# PowerResetBrd.net
KiCad netlist of a schematic drawn in EAGLE
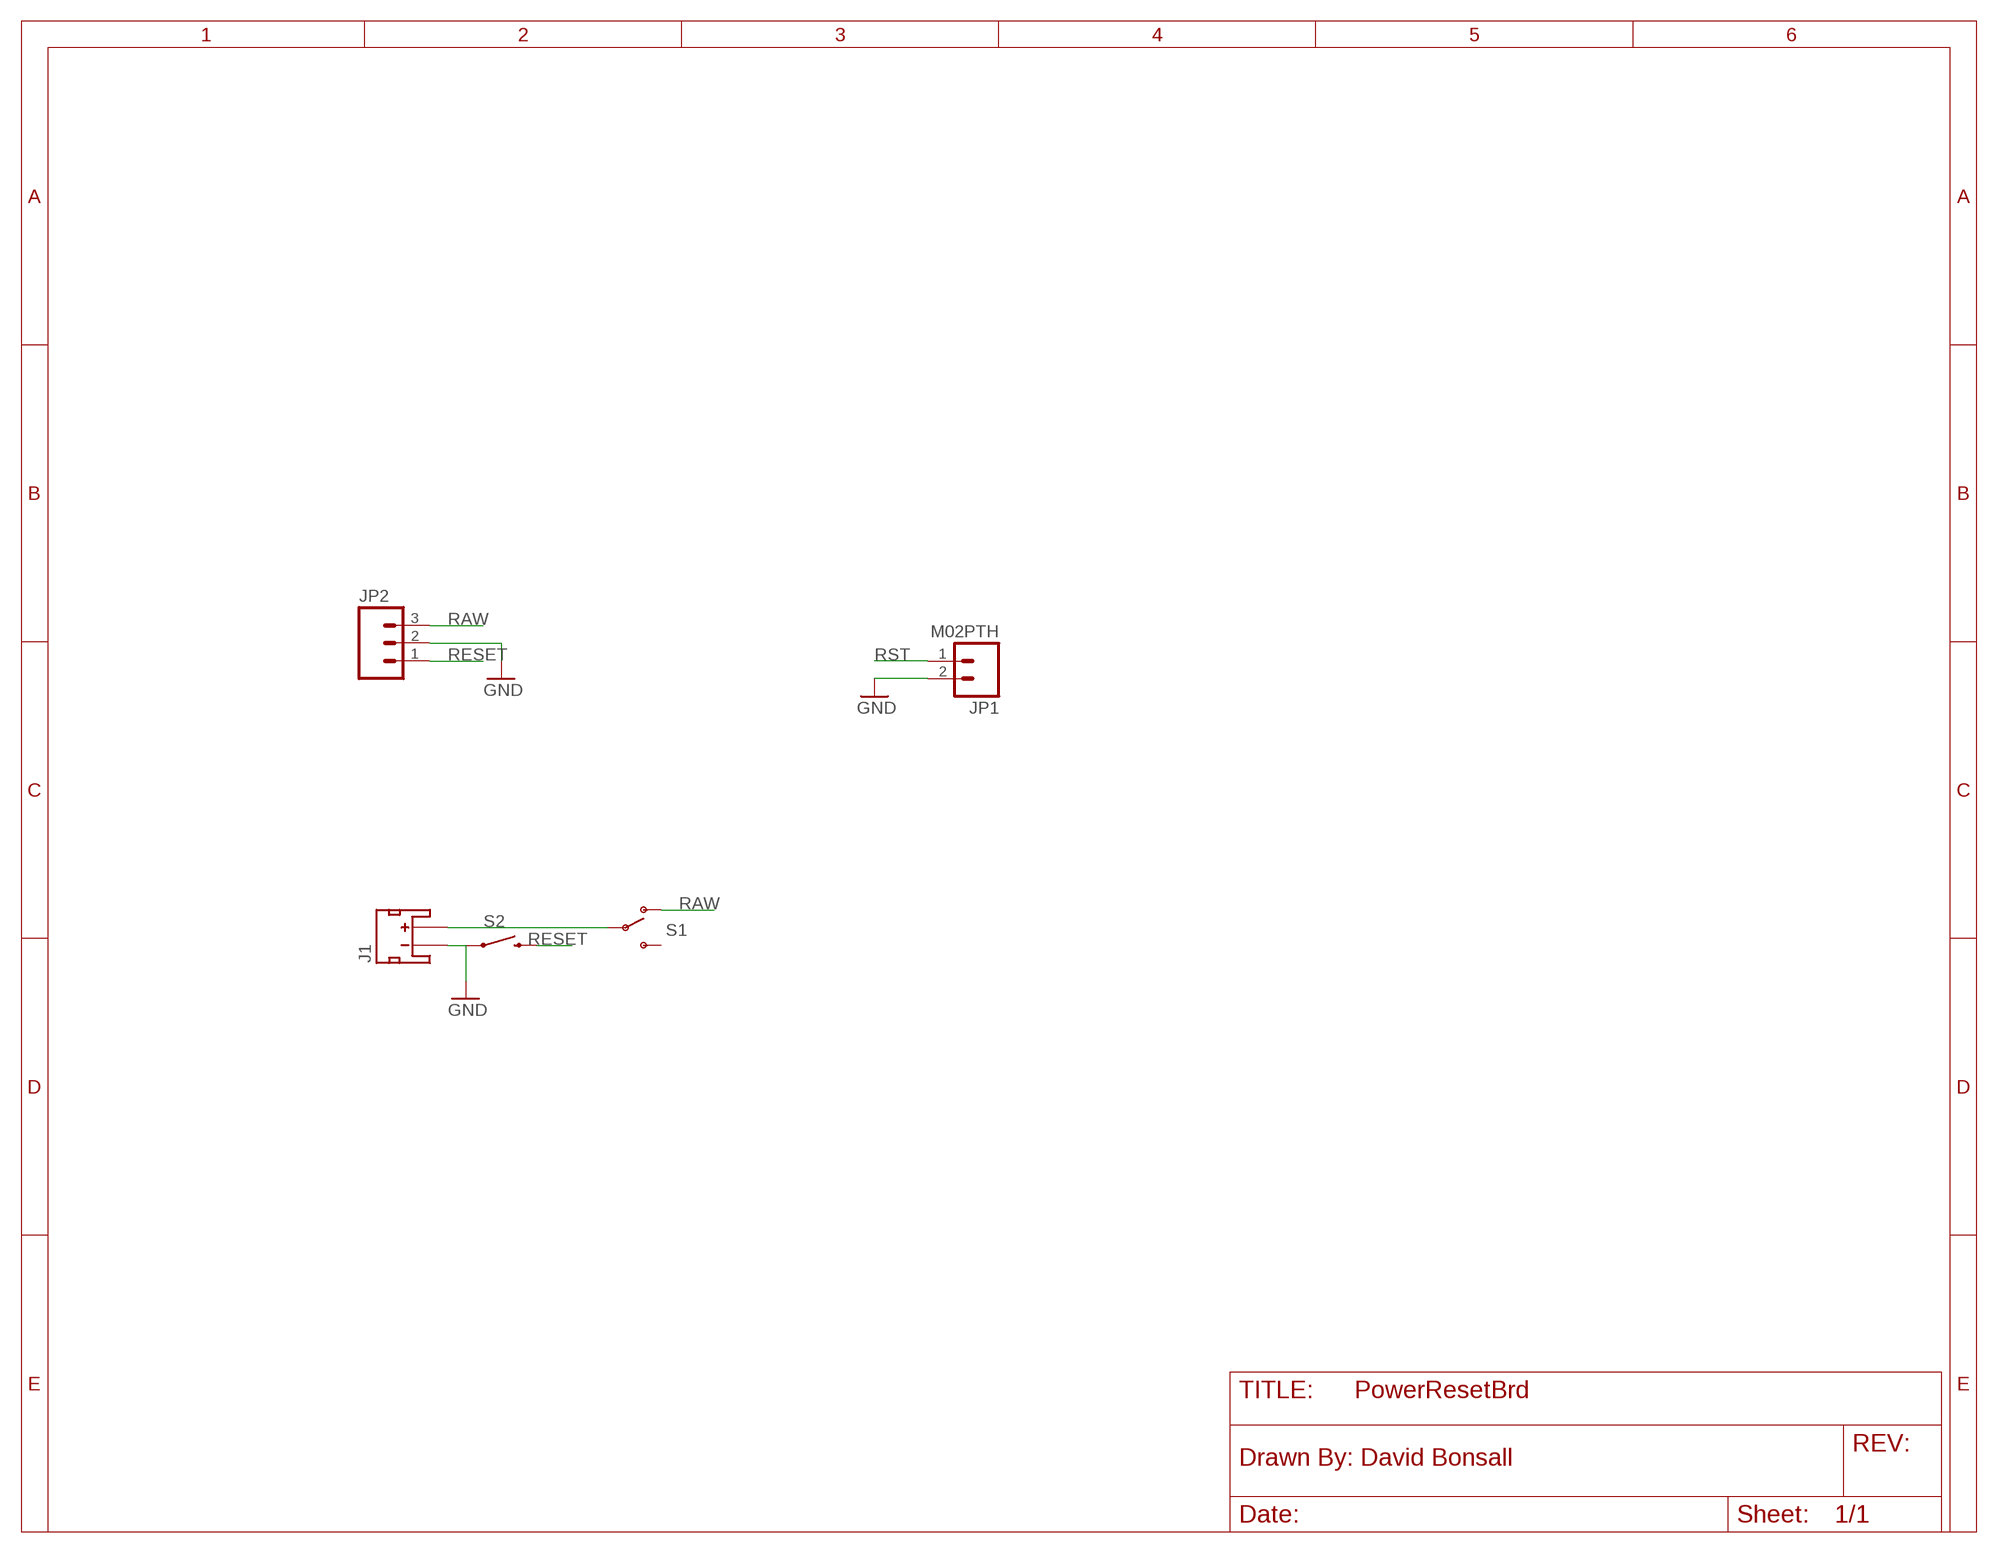
[diagram p0: schematic, sheet 1]

(export (version "E")
  (design (tool "Eeschema 10.0.6"))
  (components
    (comp (ref "J1")
      (value "JST_2MM_MALE")
      (footprint "eagle-import:JST-2-SMD")
      (libsource (lib "eagle-import") (part "JST_2MM_MALE"))
    )
    (comp (ref "JP1")
      (value "M02PTH")
      (footprint "eagle-import:1X02")
      (libsource (lib "eagle-import") (part "M02PTH"))
    )
    (comp (ref "JP2")
      (value "M03PTH")
      (footprint "eagle-import:1X03")
      (libsource (lib "eagle-import") (part "M03PTH"))
    )
    (comp (ref "S1")
      (value "SWITCH-SPDTPTH")
      (footprint "eagle-import:SWITCH-SPDT")
      (libsource (lib "eagle-import") (part "SWITCH-SPDTPTH"))
    )
    (comp (ref "S2")
      (value "SWITCH-MOMENTARY-2PTH")
      (footprint "eagle-import:TACTILE-PTH")
      (libsource (lib "eagle-import") (part "SWITCH-MOMENTARY-2PTH"))
    )
  )
  (nets
    (net (code "1") (name "/RAW") (class "Default")
      (node (ref "JP2") (pin "3") (pinfunction "3_3") (pintype "passive"))
      (node (ref "S1") (pin "1") (pinfunction "O_1") (pintype "passive"))
    )
    (net (code "2") (name "/RESET") (class "Default")
      (node (ref "JP2") (pin "1") (pinfunction "1_1") (pintype "passive"))
      (node (ref "S2") (pin "3") (pinfunction "2_3") (pintype "passive"))
    )
    (net (code "3") (name "/RST") (class "Default")
      (node (ref "JP1") (pin "1") (pinfunction "1_1") (pintype "passive"))
    )
    (net (code "4") (name "GND") (class "Default")
      (node (ref "J1") (pin "1") (pinfunction "-_1") (pintype "bidirectional"))
      (node (ref "JP1") (pin "2") (pinfunction "2_2") (pintype "passive"))
      (node (ref "JP2") (pin "2") (pinfunction "2_2") (pintype "passive"))
      (node (ref "S2") (pin "1") (pinfunction "1_1") (pintype "passive"))
    )
    (net (code "5") (name "Net-(J1-+)") (class "Default")
      (node (ref "J1") (pin "2") (pinfunction "+_2") (pintype "bidirectional"))
      (node (ref "S1") (pin "2") (pinfunction "P_2") (pintype "passive"))
    )
    (net (code "6") (name "unconnected-(J1-PAD1-PadNC1)") (class "Default")
      (node (ref "J1") (pin "NC1") (pinfunction "PAD1_NC1") (pintype "bidirectional"))
    )
    (net (code "7") (name "unconnected-(J1-PAD2-PadNC2)") (class "Default")
      (node (ref "J1") (pin "NC2") (pinfunction "PAD2_NC2") (pintype "bidirectional"))
    )
    (net (code "8") (name "unconnected-(S1-S-Pad3)") (class "Default")
      (node (ref "S1") (pin "3") (pinfunction "S_3") (pintype "passive"))
    )
  )
)
